# openmv.net
KiCad netlist of a schematic drawn in EAGLE
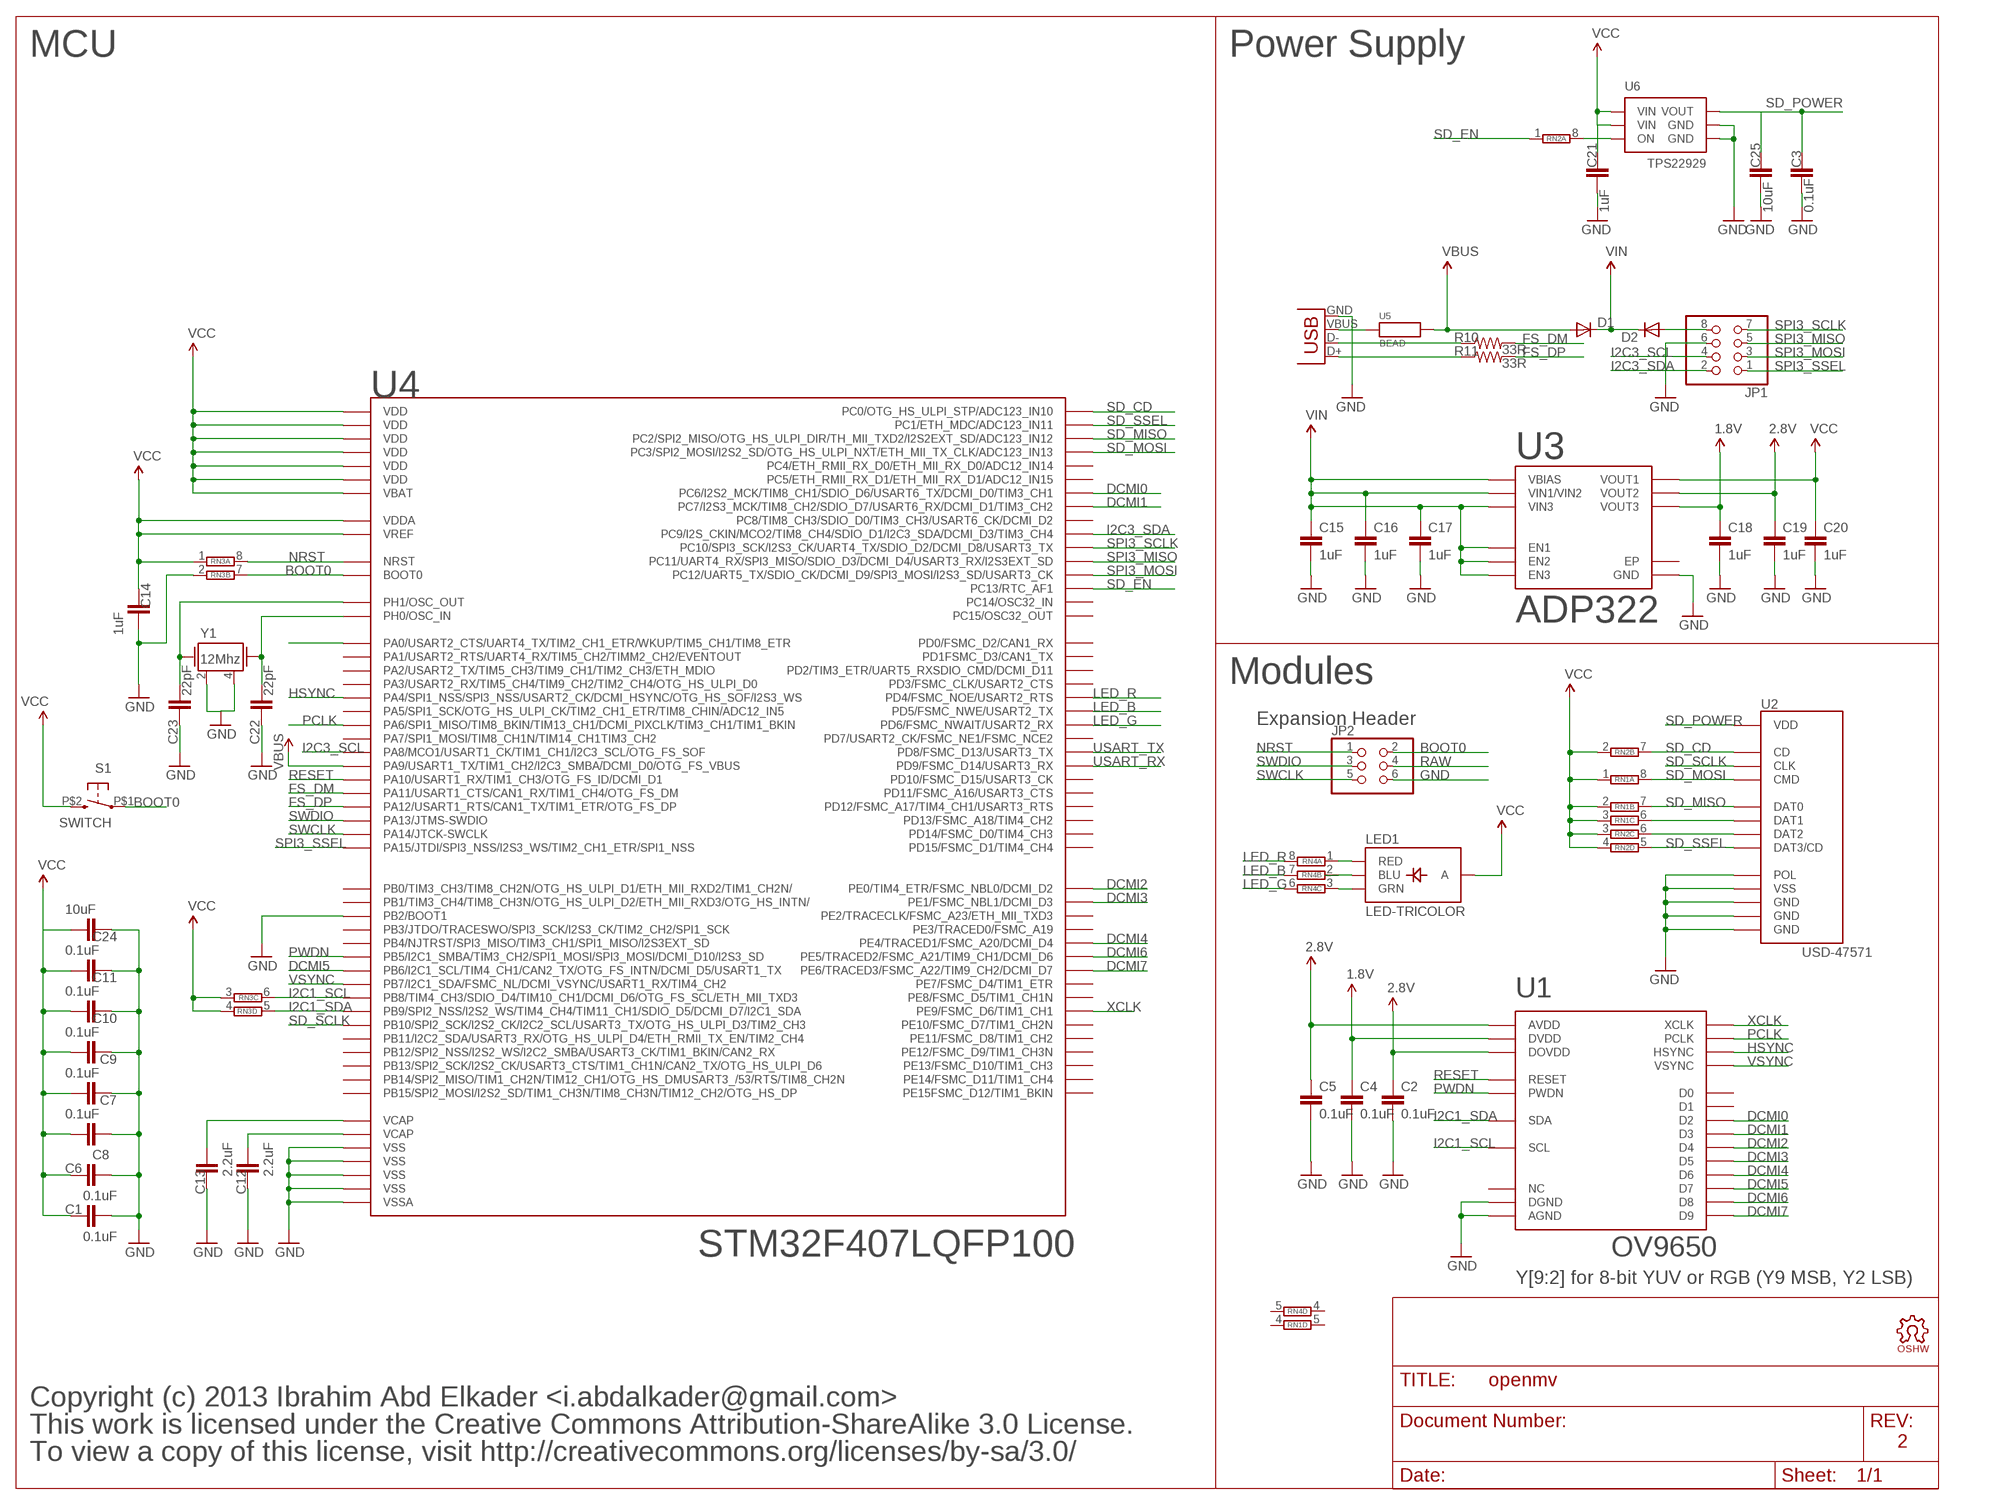
[diagram p0: schematic, sheet 1]

(export (version "E")
  (design (tool "Eeschema 10.0.6"))
  (components
    (comp (ref "C1")
      (value "0.1uF")
      (footprint "eagle-import:0402-CAP")
      (libsource (lib "eagle-import") (part "CAP0402-CAP"))
    )
    (comp (ref "C2")
      (value "0.1uF")
      (footprint "eagle-import:0402-CAP")
      (libsource (lib "eagle-import") (part "CAP0402-CAP"))
    )
    (comp (ref "C3")
      (value "0.1uF")
      (footprint "eagle-import:0402-CAP")
      (libsource (lib "eagle-import") (part "CAP0402-CAP"))
    )
    (comp (ref "C4")
      (value "0.1uF")
      (footprint "eagle-import:0402-CAP")
      (libsource (lib "eagle-import") (part "CAP0402-CAP"))
    )
    (comp (ref "C5")
      (value "0.1uF")
      (footprint "eagle-import:0402-CAP")
      (libsource (lib "eagle-import") (part "CAP0402-CAP"))
    )
    (comp (ref "C6")
      (value "0.1uF")
      (footprint "eagle-import:0402-CAP")
      (libsource (lib "eagle-import") (part "CAP0402-CAP"))
    )
    (comp (ref "C7")
      (value "0.1uF")
      (footprint "eagle-import:0402-CAP")
      (libsource (lib "eagle-import") (part "CAP0402-CAP"))
    )
    (comp (ref "C8")
      (value "0.1uF")
      (footprint "eagle-import:0402-CAP")
      (libsource (lib "eagle-import") (part "CAP0402-CAP"))
    )
    (comp (ref "C9")
      (value "0.1uF")
      (footprint "eagle-import:0402-CAP")
      (libsource (lib "eagle-import") (part "CAP0402-CAP"))
    )
    (comp (ref "C10")
      (value "0.1uF")
      (footprint "eagle-import:0402-CAP")
      (libsource (lib "eagle-import") (part "CAP0402-CAP"))
    )
    (comp (ref "C11")
      (value "0.1uF")
      (footprint "eagle-import:0402-CAP")
      (libsource (lib "eagle-import") (part "CAP0402-CAP"))
    )
    (comp (ref "C12")
      (value "2.2uF")
      (footprint "eagle-import:0402-CAP")
      (libsource (lib "eagle-import") (part "CAP0402-CAP"))
    )
    (comp (ref "C13")
      (value "2.2uF")
      (footprint "eagle-import:0402-CAP")
      (libsource (lib "eagle-import") (part "CAP0402-CAP"))
    )
    (comp (ref "C14")
      (value "1uF")
      (footprint "eagle-import:0402-CAP")
      (libsource (lib "eagle-import") (part "CAP0402-CAP"))
    )
    (comp (ref "C15")
      (value "1uF")
      (footprint "eagle-import:0402-CAP")
      (libsource (lib "eagle-import") (part "CAP0402-CAP"))
    )
    (comp (ref "C16")
      (value "1uF")
      (footprint "eagle-import:0402-CAP")
      (libsource (lib "eagle-import") (part "CAP0402-CAP"))
    )
    (comp (ref "C17")
      (value "1uF")
      (footprint "eagle-import:0402-CAP")
      (libsource (lib "eagle-import") (part "CAP0402-CAP"))
    )
    (comp (ref "C18")
      (value "1uF")
      (footprint "eagle-import:0402-CAP")
      (libsource (lib "eagle-import") (part "CAP0402-CAP"))
    )
    (comp (ref "C19")
      (value "1uF")
      (footprint "eagle-import:0402-CAP")
      (libsource (lib "eagle-import") (part "CAP0402-CAP"))
    )
    (comp (ref "C20")
      (value "1uF")
      (footprint "eagle-import:0402-CAP")
      (libsource (lib "eagle-import") (part "CAP0402-CAP"))
    )
    (comp (ref "C21")
      (value "1uF")
      (footprint "eagle-import:0402-CAP")
      (libsource (lib "eagle-import") (part "CAP0402-CAP"))
    )
    (comp (ref "C22")
      (value "22pF")
      (footprint "eagle-import:0402-CAP")
      (libsource (lib "eagle-import") (part "CAP0402-CAP"))
    )
    (comp (ref "C23")
      (value "22pF")
      (footprint "eagle-import:0402-CAP")
      (libsource (lib "eagle-import") (part "CAP0402-CAP"))
    )
    (comp (ref "C24")
      (value "10uF")
      (footprint "eagle-import:0805")
      (libsource (lib "eagle-import") (part "CAP0805"))
    )
    (comp (ref "C25")
      (value "10uF")
      (footprint "eagle-import:0805")
      (libsource (lib "eagle-import") (part "CAP0805"))
    )
    (comp (ref "D1")
      (value "DIODESOD")
      (footprint "eagle-import:SOD-323")
      (libsource (lib "eagle-import") (part "DIODESOD"))
    )
    (comp (ref "D2")
      (value "DIODESOD")
      (footprint "eagle-import:SOD-323")
      (libsource (lib "eagle-import") (part "DIODESOD"))
    )
    (comp (ref "JP1")
      (value "PINHD-2X4")
      (footprint "eagle-import:2X04")
      (libsource (lib "eagle-import") (part "PINHD-2X4"))
    )
    (comp (ref "JP2")
      (value "PINHD-2X3")
      (footprint "eagle-import:2X03")
      (libsource (lib "eagle-import") (part "PINHD-2X3"))
    )
    (comp (ref "LED1")
      (value "LED-TRICOLOR")
      (footprint "eagle-import:LED-TRICOLOR-SMD")
      (libsource (lib "eagle-import") (part "LED-TRICOLOR"))
    )
    (comp (ref "LOGO1")
      (value "OSHW_LOGO_FILLX0150-NT")
      (footprint "eagle-import:OSHW_FILLX150_NOTEXT")
      (libsource (lib "eagle-import") (part "OSHW_LOGO_FILLX0150-NT"))
    )
    (comp (ref "R10")
      (value "33R")
      (footprint "eagle-import:0402-RES")
      (libsource (lib "eagle-import") (part "RESISTOR0402-RES"))
    )
    (comp (ref "R11")
      (value "33R")
      (footprint "eagle-import:0402-RES")
      (libsource (lib "eagle-import") (part "RESISTOR0402-RES"))
    )
    (comp (ref "RN1")
      (value "4R-NCAT16")
      (footprint "eagle-import:CAT16")
      (fields (field (name "OC_FARNELL") "unknown") (field (name "OC_NEWARK") "unknown"))
      (libsource (lib "eagle-import") (part "4R-NCAT16"))
    )
    (comp (ref "RN2")
      (value "4R-NCAT16")
      (footprint "eagle-import:CAT16")
      (fields (field (name "OC_FARNELL") "unknown") (field (name "OC_NEWARK") "unknown"))
      (libsource (lib "eagle-import") (part "4R-NCAT16"))
    )
    (comp (ref "RN3")
      (value "4R-NCAT16")
      (footprint "eagle-import:CAT16")
      (libsource (lib "eagle-import") (part "4R-NCAT16"))
    )
    (comp (ref "RN4")
      (value "4R-NCAT16")
      (footprint "eagle-import:CAT16")
      (fields (field (name "OC_FARNELL") "unknown") (field (name "OC_NEWARK") "unknown"))
      (libsource (lib "eagle-import") (part "4R-NCAT16"))
    )
    (comp (ref "S1")
      (value "SWITCH")
      (footprint "eagle-import:B3U-1000P")
      (libsource (lib "eagle-import") (part "SWITCH"))
    )
    (comp (ref "U1")
      (value "OV9650")
      (footprint "eagle-import:OV9650")
      (libsource (lib "eagle-import") (part "OV9650"))
    )
    (comp (ref "U2")
      (value "USD-47571")
      (footprint "eagle-import:USD-47571")
      (libsource (lib "eagle-import") (part "USD-47571"))
    )
    (comp (ref "U3")
      (value "ADP322")
      (footprint "eagle-import:WFQFN-16")
      (libsource (lib "eagle-import") (part "ADP322"))
    )
    (comp (ref "U4")
      (value "STM32F407LQFP100")
      (footprint "eagle-import:LQFP100")
      (libsource (lib "eagle-import") (part "STM32F407LQFP100"))
    )
    (comp (ref "U5")
      (value "BEAD")
      (footprint "eagle-import:0402-CAP")
      (libsource (lib "eagle-import") (part "BEAD"))
    )
    (comp (ref "U6")
      (value "TPS22929")
      (footprint "eagle-import:SOT23-6")
      (libsource (lib "eagle-import") (part "TPS22929"))
    )
    (comp (ref "X1")
      (value "USB-MICROB")
      (footprint "eagle-import:USB-MICROB")
      (libsource (lib "eagle-import") (part "USB-MICROB"))
    )
    (comp (ref "Y1")
      (value "12Mhz")
      (footprint "eagle-import:CRYSTAL-SMD-5X3")
      (libsource (lib "eagle-import") (part "CRYSTAL5X3"))
    )
  )
  (nets
    (net (code "1") (name "/BOOT0") (class "Default")
      (node (ref "JP2") (pin "2") (pinfunction "2_2") (pintype "passive"))
      (node (ref "RN3") (pin "7") (pinfunction "2_7") (pintype "passive"))
      (node (ref "S1") (pin "P$1") (pinfunction "1_P$1") (pintype "passive"))
      (node (ref "U4") (pin "94") (pinfunction "BOOT0_94") (pintype "bidirectional"))
    )
    (net (code "2") (name "/DCMI0") (class "Default")
      (node (ref "U1") (pin "P$19") (pinfunction "D2_P$19") (pintype "bidirectional"))
      (node (ref "U4") (pin "63") (pinfunction "PC6/I2S2_MCK/TIM8_CH1/SDIO_D6/USART6_TX/DCMI_D0/TIM3_CH1_63") (pintype "bidirectional"))
    )
    (net (code "3") (name "/DCMI1") (class "Default")
      (node (ref "U1") (pin "P$21") (pinfunction "D3_P$21") (pintype "bidirectional"))
      (node (ref "U4") (pin "64") (pinfunction "PC7/I2S3_MCK/TIM8_CH2/SDIO_D7/USART6_RX/DCMI_D1/TIM3_CH2_64") (pintype "bidirectional"))
    )
    (net (code "4") (name "/DCMI2") (class "Default")
      (node (ref "U1") (pin "P$22") (pinfunction "D4_P$22") (pintype "bidirectional"))
      (node (ref "U4") (pin "97") (pinfunction "PE0/TIM4_ETR/FSMC_NBL0/DCMI_D2_97") (pintype "bidirectional"))
    )
    (net (code "5") (name "/DCMI3") (class "Default")
      (node (ref "U1") (pin "P$20") (pinfunction "D5_P$20") (pintype "bidirectional"))
      (node (ref "U4") (pin "98") (pinfunction "PE1/FSMC_NBL1/DCMI_D3_98") (pintype "bidirectional"))
    )
    (net (code "6") (name "/DCMI4") (class "Default")
      (node (ref "U1") (pin "P$18") (pinfunction "D6_P$18") (pintype "bidirectional"))
      (node (ref "U4") (pin "3") (pinfunction "PE4/TRACED1/FSMC_A20/DCMI_D4_3") (pintype "bidirectional"))
    )
    (net (code "7") (name "/DCMI5") (class "Default")
      (node (ref "U1") (pin "P$16") (pinfunction "D7_P$16") (pintype "bidirectional"))
      (node (ref "U4") (pin "92") (pinfunction "PB6/I2C1_SCL/TIM4_CH1/CAN2_TX/OTG_FS_INTN/DCMI_D5/USART1_TX_92") (pintype "bidirectional"))
    )
    (net (code "8") (name "/DCMI6") (class "Default")
      (node (ref "U1") (pin "P$14") (pinfunction "D8_P$14") (pintype "bidirectional"))
      (node (ref "U4") (pin "4") (pinfunction "PE5/TRACED2/FSMC_A21/TIM9_CH1/DCMI_D6_4") (pintype "bidirectional"))
    )
    (net (code "9") (name "/DCMI7") (class "Default")
      (node (ref "U1") (pin "P$12") (pinfunction "D9_P$12") (pintype "bidirectional"))
      (node (ref "U4") (pin "5") (pinfunction "PE6/TRACED3/FSMC_A22/TIM9_CH2/DCMI_D7_5") (pintype "bidirectional"))
    )
    (net (code "10") (name "/FS_DM") (class "Default")
      (node (ref "R10") (pin "2") (pinfunction "2_2") (pintype "passive"))
      (node (ref "U4") (pin "70") (pinfunction "PA11/USART1_CTS/CAN1_RX/TIM1_CH4/OTG_FS_DM_70") (pintype "bidirectional"))
    )
    (net (code "11") (name "/FS_DP") (class "Default")
      (node (ref "R11") (pin "2") (pinfunction "2_2") (pintype "passive"))
      (node (ref "U4") (pin "71") (pinfunction "PA12/USART1_RTS/CAN1_TX/TIM1_ETR/OTG_FS_DP_71") (pintype "bidirectional"))
    )
    (net (code "12") (name "/HSYNC") (class "Default")
      (node (ref "U1") (pin "P$9") (pinfunction "HSYNC_P$9") (pintype "bidirectional"))
      (node (ref "U4") (pin "29") (pinfunction "PA4/SPI1_NSS/SPI3_NSS/USART2_CK/DCMI_HSYNC/OTG_HS_SOF/I2S3_WS_29") (pintype "bidirectional"))
    )
    (net (code "13") (name "/I2C1_SCL") (class "Default")
      (node (ref "RN3") (pin "6") (pinfunction "2_6") (pintype "passive"))
      (node (ref "U1") (pin "P$5") (pinfunction "SCL_P$5") (pintype "bidirectional"))
      (node (ref "U4") (pin "95") (pinfunction "PB8/TIM4_CH3/SDIO_D4/TIM10_CH1/DCMI_D6/OTG_FS_SCL/ETH_MII_TXD3_95") (pintype "bidirectional"))
    )
    (net (code "14") (name "/I2C1_SDA") (class "Default")
      (node (ref "RN3") (pin "5") (pinfunction "2_5") (pintype "passive"))
      (node (ref "U1") (pin "P$3") (pinfunction "SDA_P$3") (pintype "bidirectional"))
      (node (ref "U4") (pin "96") (pinfunction "PB9/SPI2_NSS/I2S2_WS/TIM4_CH4/TIM11_CH1/SDIO_D5/DCMI_D7/I2C1_SDA_96") (pintype "bidirectional"))
    )
    (net (code "15") (name "/I2C3_SCL") (class "Default")
      (node (ref "JP1") (pin "4") (pinfunction "4_4") (pintype "passive"))
      (node (ref "U4") (pin "67") (pinfunction "PA8/MCO1/USART1_CK/TIM1_CH1/I2C3_SCL/OTG_FS_SOF_67") (pintype "bidirectional"))
    )
    (net (code "16") (name "/I2C3_SDA") (class "Default")
      (node (ref "JP1") (pin "2") (pinfunction "2_2") (pintype "passive"))
      (node (ref "U4") (pin "66") (pinfunction "PC9/I2S_CKIN/MCO2/TIM8_CH4/SDIO_D1/I2C3_SDA/DCMI_D3/TIM3_CH4_66") (pintype "bidirectional"))
    )
    (net (code "17") (name "/LED_B") (class "Default")
      (node (ref "RN4") (pin "7") (pinfunction "2_7") (pintype "passive"))
      (node (ref "U4") (pin "86") (pinfunction "PD5/FSMC_NWE/USART2_TX_86") (pintype "bidirectional"))
    )
    (net (code "18") (name "/LED_G") (class "Default")
      (node (ref "RN4") (pin "6") (pinfunction "2_6") (pintype "passive"))
      (node (ref "U4") (pin "87") (pinfunction "PD6/FSMC_NWAIT/USART2_RX_87") (pintype "bidirectional"))
    )
    (net (code "19") (name "/LED_R") (class "Default")
      (node (ref "RN4") (pin "8") (pinfunction "2_8") (pintype "passive"))
      (node (ref "U4") (pin "85") (pinfunction "PD4/FSMC_NOE/USART2_RTS_85") (pintype "bidirectional"))
    )
    (net (code "20") (name "/NRST") (class "Default")
      (node (ref "JP2") (pin "1") (pinfunction "1_1") (pintype "passive"))
      (node (ref "RN3") (pin "8") (pinfunction "2_8") (pintype "passive"))
      (node (ref "U4") (pin "14") (pinfunction "NRST_14") (pintype "bidirectional"))
    )
    (net (code "21") (name "/PCLK") (class "Default")
      (node (ref "U1") (pin "P$17") (pinfunction "PCLK_P$17") (pintype "bidirectional"))
      (node (ref "U4") (pin "31") (pinfunction "PA6/SPI1_MISO/TIM8_BKIN/TIM13_CH1/DCMI_PIXCLK/TIM3_CH1/TIM1_BKIN_31") (pintype "bidirectional"))
    )
    (net (code "22") (name "/PWDN") (class "Default")
      (node (ref "U1") (pin "P$8") (pinfunction "PWDN_P$8") (pintype "bidirectional"))
      (node (ref "U4") (pin "91") (pinfunction "PB5/I2C1_SMBA/TIM3_CH2/SPI1_MOSI/SPI3_MOSI/DCMI_D10/I2S3_SD_91") (pintype "bidirectional"))
    )
    (net (code "23") (name "/RAW") (class "Default")
      (node (ref "D2") (pin "2") (pinfunction "A_2") (pintype "passive"))
      (node (ref "JP1") (pin "8") (pinfunction "8_8") (pintype "passive"))
      (node (ref "JP2") (pin "4") (pinfunction "4_4") (pintype "passive"))
    )
    (net (code "24") (name "/RESET") (class "Default")
      (node (ref "U1") (pin "P$6") (pinfunction "RESET_P$6") (pintype "bidirectional"))
      (node (ref "U4") (pin "69") (pinfunction "PA10/USART1_RX/TIM1_CH3/OTG_FS_ID/DCMI_D1_69") (pintype "bidirectional"))
    )
    (net (code "25") (name "/SD_CD") (class "Default")
      (node (ref "RN2") (pin "7") (pinfunction "2_7") (pintype "passive"))
      (node (ref "U2") (pin "G$5") (pinfunction "CD_G$5") (pintype "power_in"))
      (node (ref "U4") (pin "15") (pinfunction "PC0/OTG_HS_ULPI_STP/ADC123_IN10_15") (pintype "bidirectional"))
    )
    (net (code "26") (name "/SD_EN") (class "Default")
      (node (ref "RN2") (pin "1") (pinfunction "1_1") (pintype "passive"))
      (node (ref "U4") (pin "7") (pinfunction "PC13/RTC_AF1_7") (pintype "bidirectional"))
    )
    (net (code "27") (name "/SD_MISO") (class "Default")
      (node (ref "RN1") (pin "7") (pinfunction "2_7") (pintype "passive"))
      (node (ref "U2") (pin "P$7") (pinfunction "DAT0_P$7") (pintype "bidirectional"))
      (node (ref "U4") (pin "17") (pinfunction "PC2/SPI2_MISO/OTG_HS_ULPI_DIR/TH_MII_TXD2/I2S2EXT_SD/ADC123_IN12_17") (pintype "bidirectional"))
    )
    (net (code "28") (name "/SD_MOSI") (class "Default")
      (node (ref "RN1") (pin "8") (pinfunction "2_8") (pintype "passive"))
      (node (ref "U2") (pin "P$3") (pinfunction "CMD_P$3") (pintype "bidirectional"))
      (node (ref "U4") (pin "18") (pinfunction "PC3/SPI2_MOSI/I2S2_SD/OTG_HS_ULPI_NXT/ETH_MII_TX_CLK/ADC123_IN13_18") (pintype "bidirectional"))
    )
    (net (code "29") (name "/SD_POWER") (class "Default")
      (node (ref "C25") (pin "1") (pinfunction "1_1") (pintype "passive"))
      (node (ref "C3") (pin "1") (pinfunction "1_1") (pintype "passive"))
      (node (ref "U2") (pin "P$4") (pinfunction "VDD_P$4") (pintype "power_in"))
      (node (ref "U6") (pin "1") (pinfunction "VOUT_1") (pintype "power_in"))
    )
    (net (code "30") (name "/SD_SCLK") (class "Default")
      (node (ref "U2") (pin "P$5") (pinfunction "CLK_P$5") (pintype "bidirectional"))
      (node (ref "U4") (pin "47") (pinfunction "PB10/SPI2_SCK/I2S2_CK/I2C2_SCL/USART3_TX/OTG_HS_ULPI_D3/TIM2_CH3_47") (pintype "bidirectional"))
    )
    (net (code "31") (name "/SD_SSEL") (class "Default")
      (node (ref "RN2") (pin "5") (pinfunction "2_5") (pintype "passive"))
      (node (ref "U2") (pin "P$2") (pinfunction "DAT3/CD_P$2") (pintype "bidirectional"))
      (node (ref "U4") (pin "16") (pinfunction "PC1/ETH_MDC/ADC123_IN11_16") (pintype "bidirectional"))
    )
    (net (code "32") (name "/SPI3_MISO") (class "Default")
      (node (ref "JP1") (pin "5") (pinfunction "5_5") (pintype "passive"))
      (node (ref "U4") (pin "79") (pinfunction "PC11/UART4_RX/SPI3_MISO/SDIO_D3/DCMI_D4/USART3_RX/I2S3EXT_SD_79") (pintype "bidirectional"))
    )
    (net (code "33") (name "/SPI3_MOSI") (class "Default")
      (node (ref "JP1") (pin "3") (pinfunction "3_3") (pintype "passive"))
      (node (ref "U4") (pin "80") (pinfunction "PC12/UART5_TX/SDIO_CK/DCMI_D9/SPI3_MOSI/I2S3_SD/USART3_CK_80") (pintype "bidirectional"))
    )
    (net (code "34") (name "/SPI3_SCLK") (class "Default")
      (node (ref "JP1") (pin "7") (pinfunction "7_7") (pintype "passive"))
      (node (ref "U4") (pin "78") (pinfunction "PC10/SPI3_SCK/I2S3_CK/UART4_TX/SDIO_D2/DCMI_D8/USART3_TX_78") (pintype "bidirectional"))
    )
    (net (code "35") (name "/SPI3_SSEL") (class "Default")
      (node (ref "JP1") (pin "1") (pinfunction "1_1") (pintype "passive"))
      (node (ref "U4") (pin "77") (pinfunction "PA15/JTDI/SPI3_NSS/I2S3_WS/TIM2_CH1_ETR/SPI1_NSS_77") (pintype "bidirectional"))
    )
    (net (code "36") (name "/SWCLK") (class "Default")
      (node (ref "JP2") (pin "5") (pinfunction "5_5") (pintype "passive"))
      (node (ref "U4") (pin "76") (pinfunction "PA14/JTCK-SWCLK_76") (pintype "bidirectional"))
    )
    (net (code "37") (name "/SWDIO") (class "Default")
      (node (ref "JP2") (pin "3") (pinfunction "3_3") (pintype "passive"))
      (node (ref "U4") (pin "72") (pinfunction "PA13/JTMS-SWDIO_72") (pintype "bidirectional"))
    )
    (net (code "38") (name "/USART_RX") (class "Default")
      (node (ref "U4") (pin "56") (pinfunction "PD9/FSMC_D14/USART3_RX_56") (pintype "bidirectional"))
    )
    (net (code "39") (name "/USART_TX") (class "Default")
      (node (ref "U4") (pin "55") (pinfunction "PD8/FSMC_D13/USART3_TX_55") (pintype "bidirectional"))
    )
    (net (code "40") (name "/VSYNC") (class "Default")
      (node (ref "U1") (pin "P$7") (pinfunction "VSYNC_P$7") (pintype "bidirectional"))
      (node (ref "U4") (pin "93") (pinfunction "PB7/I2C1_SDA/FSMC_NL/DCMI_VSYNC/USART1_RX/TIM4_CH2_93") (pintype "bidirectional"))
    )
    (net (code "41") (name "/XCLK") (class "Default")
      (node (ref "U1") (pin "P$13") (pinfunction "XCLK_P$13") (pintype "bidirectional"))
      (node (ref "U4") (pin "40") (pinfunction "PE9/FSMC_D6/TIM1_CH1_40") (pintype "bidirectional"))
    )
    (net (code "42") (name "1.8V") (class "Default")
      (node (ref "C18") (pin "1") (pinfunction "1_1") (pintype "passive"))
      (node (ref "C4") (pin "1") (pinfunction "1_1") (pintype "passive"))
      (node (ref "U1") (pin "P$10") (pinfunction "DVDD_P$10") (pintype "bidirectional"))
      (node (ref "U3") (pin "8") (pinfunction "VOUT3_8") (pintype "passive"))
    )
    (net (code "43") (name "2.8V") (class "Default")
      (node (ref "C19") (pin "1") (pinfunction "1_1") (pintype "passive"))
      (node (ref "C2") (pin "1") (pinfunction "1_1") (pintype "passive"))
      (node (ref "C5") (pin "1") (pinfunction "1_1") (pintype "passive"))
      (node (ref "U1") (pin "P$11") (pinfunction "DOVDD_P$11") (pintype "bidirectional"))
      (node (ref "U1") (pin "P$4") (pinfunction "AVDD_P$4") (pintype "power_in"))
      (node (ref "U3") (pin "6") (pinfunction "VOUT2_6") (pintype "passive"))
    )
    (net (code "44") (name "GND") (class "Default")
      (node (ref "C1") (pin "1") (pinfunction "1_1") (pintype "passive"))
      (node (ref "C10") (pin "2") (pinfunction "2_2") (pintype "passive"))
      (node (ref "C11") (pin "2") (pinfunction "2_2") (pintype "passive"))
      (node (ref "C12") (pin "2") (pinfunction "2_2") (pintype "passive"))
      (node (ref "C13") (pin "2") (pinfunction "2_2") (pintype "passive"))
      (node (ref "C14") (pin "1") (pinfunction "1_1") (pintype "passive"))
      (node (ref "C15") (pin "2") (pinfunction "2_2") (pintype "passive"))
      (node (ref "C16") (pin "2") (pinfunction "2_2") (pintype "passive"))
      (node (ref "C17") (pin "2") (pinfunction "2_2") (pintype "passive"))
      (node (ref "C18") (pin "2") (pinfunction "2_2") (pintype "passive"))
      (node (ref "C19") (pin "2") (pinfunction "2_2") (pintype "passive"))
      (node (ref "C2") (pin "2") (pinfunction "2_2") (pintype "passive"))
      (node (ref "C20") (pin "2") (pinfunction "2_2") (pintype "passive"))
      (node (ref "C21") (pin "2") (pinfunction "2_2") (pintype "passive"))
      (node (ref "C22") (pin "2") (pinfunction "2_2") (pintype "passive"))
      (node (ref "C23") (pin "2") (pinfunction "2_2") (pintype "passive"))
      (node (ref "C24") (pin "1") (pinfunction "1_1") (pintype "passive"))
      (node (ref "C25") (pin "2") (pinfunction "2_2") (pintype "passive"))
      (node (ref "C3") (pin "2") (pinfunction "2_2") (pintype "passive"))
      (node (ref "C4") (pin "2") (pinfunction "2_2") (pintype "passive"))
      (node (ref "C5") (pin "2") (pinfunction "2_2") (pintype "passive"))
      (node (ref "C6") (pin "1") (pinfunction "1_1") (pintype "passive"))
      (node (ref "C7") (pin "2") (pinfunction "2_2") (pintype "passive"))
      (node (ref "C8") (pin "1") (pinfunction "1_1") (pintype "passive"))
      (node (ref "C9") (pin "2") (pinfunction "2_2") (pintype "passive"))
      (node (ref "JP1") (pin "6") (pinfunction "6_6") (pintype "passive"))
      (node (ref "JP2") (pin "6") (pinfunction "6_6") (pintype "passive"))
      (node (ref "RN3") (pin "2") (pinfunction "1_2") (pintype "passive"))
      (node (ref "U1") (pin "P$15") (pinfunction "DGND_P$15") (pintype "bidirectional"))
      (node (ref "U1") (pin "P$2") (pinfunction "AGND_P$2") (pintype "power_in"))
      (node (ref "U2") (pin "G$1") (pinfunction "GND_G$1") (pintype "power_in"))
      (node (ref "U2") (pin "G$2") (pinfunction "GND_G$2") (pintype "power_in"))
      (node (ref "U2") (pin "G$3") (pinfunction "GND_G$3") (pintype "power_in"))
      (node (ref "U2") (pin "G$4") (pinfunction "POL_G$4") (pintype "power_in"))
      (node (ref "U2") (pin "P$6") (pinfunction "VSS_P$6") (pintype "power_in"))
      (node (ref "U3") (pin "12") (pinfunction "GND_12") (pintype "power_in"))
      (node (ref "U4") (pin "10") (pinfunction "VSS_10") (pintype "power_in"))
      (node (ref "U4") (pin "20") (pinfunction "VSSA_20") (pintype "power_in"))
      (node (ref "U4") (pin "27") (pinfunction "VSS_27") (pintype "power_in"))
      (node (ref "U4") (pin "37") (pinfunction "PB2/BOOT1_37") (pintype "bidirectional"))
      (node (ref "U4") (pin "74") (pinfunction "VSS_74") (pintype "power_in"))
      (node (ref "U4") (pin "99") (pinfunction "VSS_99") (pintype "power_in"))
      (node (ref "U6") (pin "2") (pinfunction "GND_2") (pintype "power_in"))
      (node (ref "U6") (pin "5") (pinfunction "GND_5") (pintype "power_in"))
      (node (ref "X1") (pin "GND") (pinfunction "GND_GND") (pintype "bidirectional"))
      (node (ref "Y1") (pin "2") (pinfunction "P$1_2") (pintype "power_in"))
      (node (ref "Y1") (pin "4") (pinfunction "P$2_4") (pintype "power_in"))
    )
    (net (code "45") (name "Net-(C12-Pad1)") (class "Default")
      (node (ref "C12") (pin "1") (pinfunction "1_1") (pintype "passive"))
      (node (ref "U4") (pin "73") (pinfunction "VCAP_73") (pintype "power_in"))
    )
    (net (code "46") (name "Net-(C13-Pad1)") (class "Default")
      (node (ref "C13") (pin "1") (pinfunction "1_1") (pintype "passive"))
      (node (ref "U4") (pin "49") (pinfunction "VCAP_49") (pintype "power_in"))
    )
    (net (code "47") (name "Net-(LED1-BLU)") (class "Default")
      (node (ref "LED1") (pin "B") (pinfunction "BLU_B") (pintype "bidirectional"))
      (node (ref "RN4") (pin "2") (pinfunction "1_2") (pintype "passive"))
    )
    (net (code "48") (name "Net-(LED1-GRN)") (class "Default")
      (node (ref "LED1") (pin "G") (pinfunction "GRN_G") (pintype "bidirectional"))
      (node (ref "RN4") (pin "3") (pinfunction "1_3") (pintype "passive"))
    )
    (net (code "49") (name "Net-(LED1-RED)") (class "Default")
      (node (ref "LED1") (pin "R") (pinfunction "RED_R") (pintype "bidirectional"))
      (node (ref "RN4") (pin "1") (pinfunction "1_1") (pintype "passive"))
    )
    (net (code "50") (name "Net-(R10-Pad1)") (class "Default")
      (node (ref "R10") (pin "1") (pinfunction "1_1") (pintype "passive"))
      (node (ref "X1") (pin "D-") (pinfunction "D-_D-") (pintype "bidirectional"))
    )
    (net (code "51") (name "Net-(R11-Pad1)") (class "Default")
      (node (ref "R11") (pin "1") (pinfunction "1_1") (pintype "passive"))
      (node (ref "X1") (pin "D+") (pinfunction "D+_D+") (pintype "bidirectional"))
    )
    (net (code "52") (name "Net-(RN1C-2)") (class "Default")
      (node (ref "RN1") (pin "6") (pinfunction "2_6") (pintype "passive"))
      (node (ref "U2") (pin "P$8") (pinfunction "DAT1_P$8") (pintype "bidirectional"))
    )
    (net (code "53") (name "Net-(RN2A-2)") (class "Default")
      (node (ref "RN2") (pin "8") (pinfunction "2_8") (pintype "passive"))
      (node (ref "U6") (pin "3") (pinfunction "ON_3") (pintype "bidirectional"))
    )
    (net (code "54") (name "Net-(RN2C-2)") (class "Default")
      (node (ref "RN2") (pin "6") (pinfunction "2_6") (pintype "passive"))
      (node (ref "U2") (pin "P$1") (pinfunction "DAT2_P$1") (pintype "bidirectional"))
    )
    (net (code "55") (name "Net-(U4-PH0{slash}OSC_IN)") (class "Default")
      (node (ref "C22") (pin "1") (pinfunction "1_1") (pintype "passive"))
      (node (ref "U4") (pin "12") (pinfunction "PH0/OSC_IN_12") (pintype "bidirectional"))
      (node (ref "Y1") (pin "3") (pinfunction "2_3") (pintype "passive"))
    )
    (net (code "56") (name "Net-(U4-PH1{slash}OSC_OUT)") (class "Default")
      (node (ref "C23") (pin "1") (pinfunction "1_1") (pintype "passive"))
      (node (ref "U4") (pin "13") (pinfunction "PH1/OSC_OUT_13") (pintype "bidirectional"))
      (node (ref "Y1") (pin "1") (pinfunction "1_1") (pintype "passive"))
    )
    (net (code "57") (name "Net-(U5-Pad1)") (class "Default")
      (node (ref "U5") (pin "1") (pinfunction "1_1") (pintype "passive"))
      (node (ref "X1") (pin "VBUS") (pinfunction "VBUS_VBUS") (pintype "bidirectional"))
    )
    (net (code "58") (name "VBUS") (class "Default")
      (node (ref "D1") (pin "2") (pinfunction "A_2") (pintype "passive"))
      (node (ref "U4") (pin "68") (pinfunction "PA9/USART1_TX/TIM1_CH2/I2C3_SMBA/DCMI_D0/OTG_FS_VBUS_68") (pintype "bidirectional"))
      (node (ref "U5") (pin "2") (pinfunction "2_2") (pintype "passive"))
    )
    (net (code "59") (name "VCC") (class "Default")
      (node (ref "C1") (pin "2") (pinfunction "2_2") (pintype "passive"))
      (node (ref "C10") (pin "1") (pinfunction "1_1") (pintype "passive"))
      (node (ref "C11") (pin "1") (pinfunction "1_1") (pintype "passive"))
      (node (ref "C14") (pin "2") (pinfunction "2_2") (pintype "passive"))
      (node (ref "C20") (pin "1") (pinfunction "1_1") (pintype "passive"))
      (node (ref "C21") (pin "1") (pinfunction "1_1") (pintype "passive"))
      (node (ref "C24") (pin "2") (pinfunction "2_2") (pintype "passive"))
      (node (ref "C6") (pin "2") (pinfunction "2_2") (pintype "passive"))
      (node (ref "C7") (pin "1") (pinfunction "1_1") (pintype "passive"))
      (node (ref "C8") (pin "2") (pinfunction "2_2") (pintype "passive"))
      (node (ref "C9") (pin "1") (pinfunction "1_1") (pintype "passive"))
      (node (ref "LED1") (pin "A") (pinfunction "A_A") (pintype "bidirectional"))
      (node (ref "RN1") (pin "1") (pinfunction "1_1") (pintype "passive"))
      (node (ref "RN1") (pin "2") (pinfunction "1_2") (pintype "passive"))
      (node (ref "RN1") (pin "3") (pinfunction "1_3") (pintype "passive"))
      (node (ref "RN2") (pin "2") (pinfunction "1_2") (pintype "passive"))
      (node (ref "RN2") (pin "3") (pinfunction "1_3") (pintype "passive"))
      (node (ref "RN2") (pin "4") (pinfunction "1_4") (pintype "passive"))
      (node (ref "RN3") (pin "1") (pinfunction "1_1") (pintype "passive"))
      (node (ref "RN3") (pin "3") (pinfunction "1_3") (pintype "passive"))
      (node (ref "RN3") (pin "4") (pinfunction "1_4") (pintype "passive"))
      (node (ref "S1") (pin "P$2") (pinfunction "2_P$2") (pintype "passive"))
      (node (ref "U3") (pin "5") (pinfunction "VOUT1_5") (pintype "passive"))
      (node (ref "U4") (pin "100") (pinfunction "VDD_100") (pintype "power_in"))
      (node (ref "U4") (pin "11") (pinfunction "VDD_11") (pintype "power_in"))
      (node (ref "U4") (pin "19") (pinfunction "VDD_19") (pintype "power_in"))
      (node (ref "U4") (pin "21") (pinfunction "VREF_21") (pintype "power_in"))
      (node (ref "U4") (pin "22") (pinfunction "VDDA_22") (pintype "power_in"))
      (node (ref "U4") (pin "28") (pinfunction "VDD_28") (pintype "power_in"))
      (node (ref "U4") (pin "50") (pinfunction "VDD_50") (pintype "power_in"))
      (node (ref "U4") (pin "6") (pinfunction "VBAT_6") (pintype "power_in"))
      (node (ref "U4") (pin "75") (pinfunction "VDD_75") (pintype "power_in"))
      (node (ref "U6") (pin "4") (pinfunction "VIN_4") (pintype "power_in"))
      (node (ref "U6") (pin "6") (pinfunction "VIN_6") (pintype "power_in"))
    )
    (net (code "60") (name "VIN") (class "Default")
      (node (ref "C15") (pin "1") (pinfunction "1_1") (pintype "passive"))
      (node (ref "C16") (pin "1") (pinfunction "1_1") (pintype "passive"))
      (node (ref "C17") (pin "1") (pinfunction "1_1") (pintype "passive"))
      (node (ref "D1") (pin "1") (pinfunction "C_1") (pintype "passive"))
      (node (ref "D2") (pin "1") (pinfunction "C_1") (pintype "passive"))
      (node (ref "U3") (pin "1") (pinfunction "EN1_1") (pintype "passive"))
      (node (ref "U3") (pin "10") (pinfunction "VIN3_10") (pintype "power_in"))
      (node (ref "U3") (pin "15") (pinfunction "EN3_15") (pintype "passive"))
      (node (ref "U3") (pin "16") (pinfunction "EN2_16") (pintype "passive"))
      (node (ref "U3") (pin "2") (pinfunction "VBIAS_2") (pintype "power_in"))
      (node (ref "U3") (pin "3") (pinfunction "VIN1/VIN2_3") (pintype "power_in"))
    )
    (net (code "61") (name "unconnected-(RN1D-1-Pad4)") (class "Default")
      (node (ref "RN1") (pin "4") (pinfunction "1_4") (pintype "passive"))
    )
    (net (code "62") (name "unconnected-(RN1D-2-Pad5)") (class "Default")
      (node (ref "RN1") (pin "5") (pinfunction "2_5") (pintype "passive"))
    )
    (net (code "63") (name "unconnected-(RN4D-1-Pad4)") (class "Default")
      (node (ref "RN4") (pin "4") (pinfunction "1_4") (pintype "passive"))
    )
    (net (code "64") (name "unconnected-(RN4D-2-Pad5)") (class "Default")
      (node (ref "RN4") (pin "5") (pinfunction "2_5") (pintype "passive"))
    )
    (net (code "65") (name "unconnected-(U1-D0-PadP$24)") (class "Default")
      (node (ref "U1") (pin "P$24") (pinfunction "D0_P$24") (pintype "bidirectional"))
    )
    (net (code "66") (name "unconnected-(U1-D1-PadP$23)") (class "Default")
      (node (ref "U1") (pin "P$23") (pinfunction "D1_P$23") (pintype "bidirectional"))
    )
    (net (code "67") (name "unconnected-(U1-NC-PadP$1)") (class "Default")
      (node (ref "U1") (pin "P$1") (pinfunction "NC_P$1") (pintype "no_connect"))
    )
    (net (code "68") (name "unconnected-(U3A-EP-PadEXP)") (class "Default")
      (node (ref "U3") (pin "EXP") (pinfunction "EP_EXP") (pintype "input"))
    )
    (net (code "69") (name "unconnected-(U4-PA0{slash}USART2_CTS{slash}UART4_TX{slash}TIM2_CH1_ETR{slash}WKUP{slash}TIM5_CH1{slash}TIM8_ETR-Pad23)") (class "Default")
      (node (ref "U4") (pin "23") (pinfunction "PA0/USART2_CTS/UART4_TX/TIM2_CH1_ETR/WKUP/TIM5_CH1/TIM8_ETR_23") (pintype "bidirectional"))
    )
    (net (code "70") (name "unconnected-(U4-PA1{slash}USART2_RTS{slash}UART4_RX{slash}TIM5_CH2{slash}TIMM2_CH2{slash}EVENTOUT-Pad24)") (class "Default")
      (node (ref "U4") (pin "24") (pinfunction "PA1/USART2_RTS/UART4_RX/TIM5_CH2/TIMM2_CH2/EVENTOUT_24") (pintype "bidirectional"))
    )
    (net (code "71") (name "unconnected-(U4-PA2{slash}USART2_TX{slash}TIM5_CH3{slash}TIM9_CH1{slash}TIM2_CH3{slash}ETH_MDIO-Pad25)") (class "Default")
      (node (ref "U4") (pin "25") (pinfunction "PA2/USART2_TX/TIM5_CH3/TIM9_CH1/TIM2_CH3/ETH_MDIO_25") (pintype "bidirectional"))
    )
    (net (code "72") (name "unconnected-(U4-PA3{slash}USART2_RX{slash}TIM5_CH4{slash}TIM9_CH2{slash}TIM2_CH4{slash}OTG_HS_ULPI_D0-Pad26)") (class "Default")
      (node (ref "U4") (pin "26") (pinfunction "PA3/USART2_RX/TIM5_CH4/TIM9_CH2/TIM2_CH4/OTG_HS_ULPI_D0_26") (pintype "bidirectional"))
    )
    (net (code "73") (name "unconnected-(U4-PA5{slash}SPI1_SCK{slash}OTG_HS_ULPI_CK{slash}TIM2_CH1_ETR{slash}TIM8_CHIN{slash}ADC12_IN5-Pad30)") (class "Default")
      (node (ref "U4") (pin "30") (pinfunction "PA5/SPI1_SCK/OTG_HS_ULPI_CK/TIM2_CH1_ETR/TIM8_CHIN/ADC12_IN5_30") (pintype "bidirectional"))
    )
    (net (code "74") (name "unconnected-(U4-PA7{slash}SPI1_MOSI{slash}TIM8_CH1N{slash}TIM14_CH1TIM3_CH2-Pad32)") (class "Default")
      (node (ref "U4") (pin "32") (pinfunction "PA7/SPI1_MOSI/TIM8_CH1N/TIM14_CH1TIM3_CH2_32") (pintype "bidirectional"))
    )
    (net (code "75") (name "unconnected-(U4-PB0{slash}TIM3_CH3{slash}TIM8_CH2N{slash}OTG_HS_ULPI_D1{slash}ETH_MII_RXD2{slash}TIM1_CH2N{slash}-Pad35)") (class "Default")
      (node (ref "U4") (pin "35") (pinfunction "PB0/TIM3_CH3/TIM8_CH2N/OTG_HS_ULPI_D1/ETH_MII_RXD2/TIM1_CH2N/_35") (pintype "bidirectional"))
    )
    (net (code "76") (name "unconnected-(U4-PB1{slash}TIM3_CH4{slash}TIM8_CH3N{slash}OTG_HS_ULPI_D2{slash}ETH_MII_RXD3{slash}OTG_HS_INTN{slash}-Pad36)") (class "Default")
      (node (ref "U4") (pin "36") (pinfunction "PB1/TIM3_CH4/TIM8_CH3N/OTG_HS_ULPI_D2/ETH_MII_RXD3/OTG_HS_INTN/_36") (pintype "bidirectional"))
    )
    (net (code "77") (name "unconnected-(U4-PB3{slash}JTDO{slash}TRACESWO{slash}SPI3_SCK{slash}I2S3_CK{slash}TIM2_CH2{slash}SPI1_SCK-Pad89)") (class "Default")
      (node (ref "U4") (pin "89") (pinfunction "PB3/JTDO/TRACESWO/SPI3_SCK/I2S3_CK/TIM2_CH2/SPI1_SCK_89") (pintype "bidirectional"))
    )
    (net (code "78") (name "unconnected-(U4-PB4{slash}NJTRST{slash}SPI3_MISO{slash}TIM3_CH1{slash}SPI1_MISO{slash}I2S3EXT_SD-Pad90)") (class "Default")
      (node (ref "U4") (pin "90") (pinfunction "PB4/NJTRST/SPI3_MISO/TIM3_CH1/SPI1_MISO/I2S3EXT_SD_90") (pintype "bidirectional"))
    )
    (net (code "79") (name "unconnected-(U4-PB11{slash}I2C2_SDA{slash}USART3_RX{slash}OTG_HS_ULPI_D4{slash}ETH_RMII_TX_EN{slash}TIM2_CH4-Pad48)") (class "Default")
      (node (ref "U4") (pin "48") (pinfunction "PB11/I2C2_SDA/USART3_RX/OTG_HS_ULPI_D4/ETH_RMII_TX_EN/TIM2_CH4_48") (pintype "bidirectional"))
    )
    (net (code "80") (name "unconnected-(U4-PB12{slash}SPI2_NSS{slash}I2S2_WS{slash}I2C2_SMBA{slash}USART3_CK{slash}TIM1_BKIN{slash}CAN2_RX-Pad51)") (class "Default")
      (node (ref "U4") (pin "51") (pinfunction "PB12/SPI2_NSS/I2S2_WS/I2C2_SMBA/USART3_CK/TIM1_BKIN/CAN2_RX_51") (pintype "bidirectional"))
    )
    (net (code "81") (name "unconnected-(U4-PB13{slash}SPI2_SCK{slash}I2S2_CK{slash}USART3_CTS{slash}TIM1_CH1N{slash}CAN2_TX{slash}OTG_HS_ULPI_D6-Pad52)") (class "Default")
      (node (ref "U4") (pin "52") (pinfunction "PB13/SPI2_SCK/I2S2_CK/USART3_CTS/TIM1_CH1N/CAN2_TX/OTG_HS_ULPI_D6_52") (pintype "bidirectional"))
    )
    (net (code "82") (name "unconnected-(U4-PB14{slash}SPI2_MISO{slash}TIM1_CH2N{slash}TIM12_CH1{slash}OTG_HS_DMUSART3_{slash}53{slash}RTS{slash}TIM8_CH2N-Pad53)") (class "Default")
      (node (ref "U4") (pin "53") (pinfunction "PB14/SPI2_MISO/TIM1_CH2N/TIM12_CH1/OTG_HS_DMUSART3_/53/RTS/TIM8_CH2N_53") (pintype "bidirectional"))
    )
    (net (code "83") (name "unconnected-(U4-PB15{slash}SPI2_MOSI{slash}I2S2_SD{slash}TIM1_CH3N{slash}TIM8_CH3N{slash}TIM12_CH2{slash}OTG_HS_DP-Pad54)") (class "Default")
      (node (ref "U4") (pin "54") (pinfunction "PB15/SPI2_MOSI/I2S2_SD/TIM1_CH3N/TIM8_CH3N/TIM12_CH2/OTG_HS_DP_54") (pintype "bidirectional"))
    )
    (net (code "84") (name "unconnected-(U4-PC4{slash}ETH_RMII_RX_D0{slash}ETH_MII_RX_D0{slash}ADC12_IN14-Pad33)") (class "Default")
      (node (ref "U4") (pin "33") (pinfunction "PC4/ETH_RMII_RX_D0/ETH_MII_RX_D0/ADC12_IN14_33") (pintype "bidirectional"))
    )
    (net (code "85") (name "unconnected-(U4-PC5{slash}ETH_RMII_RX_D1{slash}ETH_MII_RX_D1{slash}ADC12_IN15-Pad34)") (class "Default")
      (node (ref "U4") (pin "34") (pinfunction "PC5/ETH_RMII_RX_D1/ETH_MII_RX_D1/ADC12_IN15_34") (pintype "bidirectional"))
    )
    (net (code "86") (name "unconnected-(U4-PC8{slash}TIM8_CH3{slash}SDIO_D0{slash}TIM3_CH3{slash}USART6_CK{slash}DCMI_D2-Pad65)") (class "Default")
      (node (ref "U4") (pin "65") (pinfunction "PC8/TIM8_CH3/SDIO_D0/TIM3_CH3/USART6_CK/DCMI_D2_65") (pintype "bidirectional"))
    )
    (net (code "87") (name "unconnected-(U4-PC14{slash}OSC32_IN-Pad8)") (class "Default")
      (node (ref "U4") (pin "8") (pinfunction "PC14/OSC32_IN_8") (pintype "bidirectional"))
    )
    (net (code "88") (name "unconnected-(U4-PC15{slash}OSC32_OUT-Pad9)") (class "Default")
      (node (ref "U4") (pin "9") (pinfunction "PC15/OSC32_OUT_9") (pintype "bidirectional"))
    )
    (net (code "89") (name "unconnected-(U4-PD0{slash}FSMC_D2{slash}CAN1_RX-Pad81)") (class "Default")
      (node (ref "U4") (pin "81") (pinfunction "PD0/FSMC_D2/CAN1_RX_81") (pintype "bidirectional"))
    )
    (net (code "90") (name "unconnected-(U4-PD1FSMC_D3{slash}CAN1_TX-Pad82)") (class "Default")
      (node (ref "U4") (pin "82") (pinfunction "PD1FSMC_D3/CAN1_TX_82") (pintype "bidirectional"))
    )
    (net (code "91") (name "unconnected-(U4-PD2{slash}TIM3_ETR{slash}UART5_RXSDIO_CMD{slash}DCMI_D11-Pad83)") (class "Default")
      (node (ref "U4") (pin "83") (pinfunction "PD2/TIM3_ETR/UART5_RXSDIO_CMD/DCMI_D11_83") (pintype "bidirectional"))
    )
    (net (code "92") (name "unconnected-(U4-PD3{slash}FSMC_CLK{slash}USART2_CTS-Pad84)") (class "Default")
      (node (ref "U4") (pin "84") (pinfunction "PD3/FSMC_CLK/USART2_CTS_84") (pintype "bidirectional"))
    )
    (net (code "93") (name "unconnected-(U4-PD7{slash}USART2_CK{slash}FSMC_NE1{slash}FSMC_NCE2-Pad88)") (class "Default")
      (node (ref "U4") (pin "88") (pinfunction "PD7/USART2_CK/FSMC_NE1/FSMC_NCE2_88") (pintype "bidirectional"))
    )
    (net (code "94") (name "unconnected-(U4-PD10{slash}FSMC_D15{slash}USART3_CK-Pad57)") (class "Default")
      (node (ref "U4") (pin "57") (pinfunction "PD10/FSMC_D15/USART3_CK_57") (pintype "bidirectional"))
    )
    (net (code "95") (name "unconnected-(U4-PD11{slash}FSMC_A16{slash}USART3_CTS-Pad58)") (class "Default")
      (node (ref "U4") (pin "58") (pinfunction "PD11/FSMC_A16/USART3_CTS_58") (pintype "bidirectional"))
    )
    (net (code "96") (name "unconnected-(U4-PD12{slash}FSMC_A17{slash}TIM4_CH1{slash}USART3_RTS-Pad59)") (class "Default")
      (node (ref "U4") (pin "59") (pinfunction "PD12/FSMC_A17/TIM4_CH1/USART3_RTS_59") (pintype "bidirectional"))
    )
    (net (code "97") (name "unconnected-(U4-PD13{slash}FSMC_A18{slash}TIM4_CH2-Pad60)") (class "Default")
      (node (ref "U4") (pin "60") (pinfunction "PD13/FSMC_A18/TIM4_CH2_60") (pintype "bidirectional"))
    )
    (net (code "98") (name "unconnected-(U4-PD14{slash}FSMC_D0{slash}TIM4_CH3-Pad61)") (class "Default")
      (node (ref "U4") (pin "61") (pinfunction "PD14/FSMC_D0/TIM4_CH3_61") (pintype "bidirectional"))
    )
    (net (code "99") (name "unconnected-(U4-PD15{slash}FSMC_D1{slash}TIM4_CH4-Pad62)") (class "Default")
      (node (ref "U4") (pin "62") (pinfunction "PD15/FSMC_D1/TIM4_CH4_62") (pintype "bidirectional"))
    )
    (net (code "100") (name "unconnected-(U4-PE2{slash}TRACECLK{slash}FSMC_A23{slash}ETH_MII_TXD3-Pad1)") (class "Default")
      (node (ref "U4") (pin "1") (pinfunction "PE2/TRACECLK/FSMC_A23/ETH_MII_TXD3_1") (pintype "bidirectional"))
    )
    (net (code "101") (name "unconnected-(U4-PE3{slash}TRACED0{slash}FSMC_A19-Pad2)") (class "Default")
      (node (ref "U4") (pin "2") (pinfunction "PE3/TRACED0/FSMC_A19_2") (pintype "bidirectional"))
    )
    (net (code "102") (name "unconnected-(U4-PE7{slash}FSMC_D4{slash}TIM1_ETR-Pad38)") (class "Default")
      (node (ref "U4") (pin "38") (pinfunction "PE7/FSMC_D4/TIM1_ETR_38") (pintype "bidirectional"))
    )
    (net (code "103") (name "unconnected-(U4-PE8{slash}FSMC_D5{slash}TIM1_CH1N-Pad39)") (class "Default")
      (node (ref "U4") (pin "39") (pinfunction "PE8/FSMC_D5/TIM1_CH1N_39") (pintype "bidirectional"))
    )
    (net (code "104") (name "unconnected-(U4-PE10{slash}FSMC_D7{slash}TIM1_CH2N-Pad41)") (class "Default")
      (node (ref "U4") (pin "41") (pinfunction "PE10/FSMC_D7/TIM1_CH2N_41") (pintype "bidirectional"))
    )
    (net (code "105") (name "unconnected-(U4-PE11{slash}FSMC_D8{slash}TIM1_CH2-Pad42)") (class "Default")
      (node (ref "U4") (pin "42") (pinfunction "PE11/FSMC_D8/TIM1_CH2_42") (pintype "bidirectional"))
    )
    (net (code "106") (name "unconnected-(U4-PE12{slash}FSMC_D9{slash}TIM1_CH3N-Pad43)") (class "Default")
      (node (ref "U4") (pin "43") (pinfunction "PE12/FSMC_D9/TIM1_CH3N_43") (pintype "bidirectional"))
    )
    (net (code "107") (name "unconnected-(U4-PE13{slash}FSMC_D10{slash}TIM1_CH3-Pad44)") (class "Default")
      (node (ref "U4") (pin "44") (pinfunction "PE13/FSMC_D10/TIM1_CH3_44") (pintype "bidirectional"))
    )
    (net (code "108") (name "unconnected-(U4-PE14{slash}FSMC_D11{slash}TIM1_CH4-Pad45)") (class "Default")
      (node (ref "U4") (pin "45") (pinfunction "PE14/FSMC_D11/TIM1_CH4_45") (pintype "bidirectional"))
    )
    (net (code "109") (name "unconnected-(U4-PE15FSMC_D12{slash}TIM1_BKIN-Pad46)") (class "Default")
      (node (ref "U4") (pin "46") (pinfunction "PE15FSMC_D12/TIM1_BKIN_46") (pintype "bidirectional"))
    )
  )
)
